# 09_-_USB.net
KiCad netlist of a schematic drawn in Altium Designer
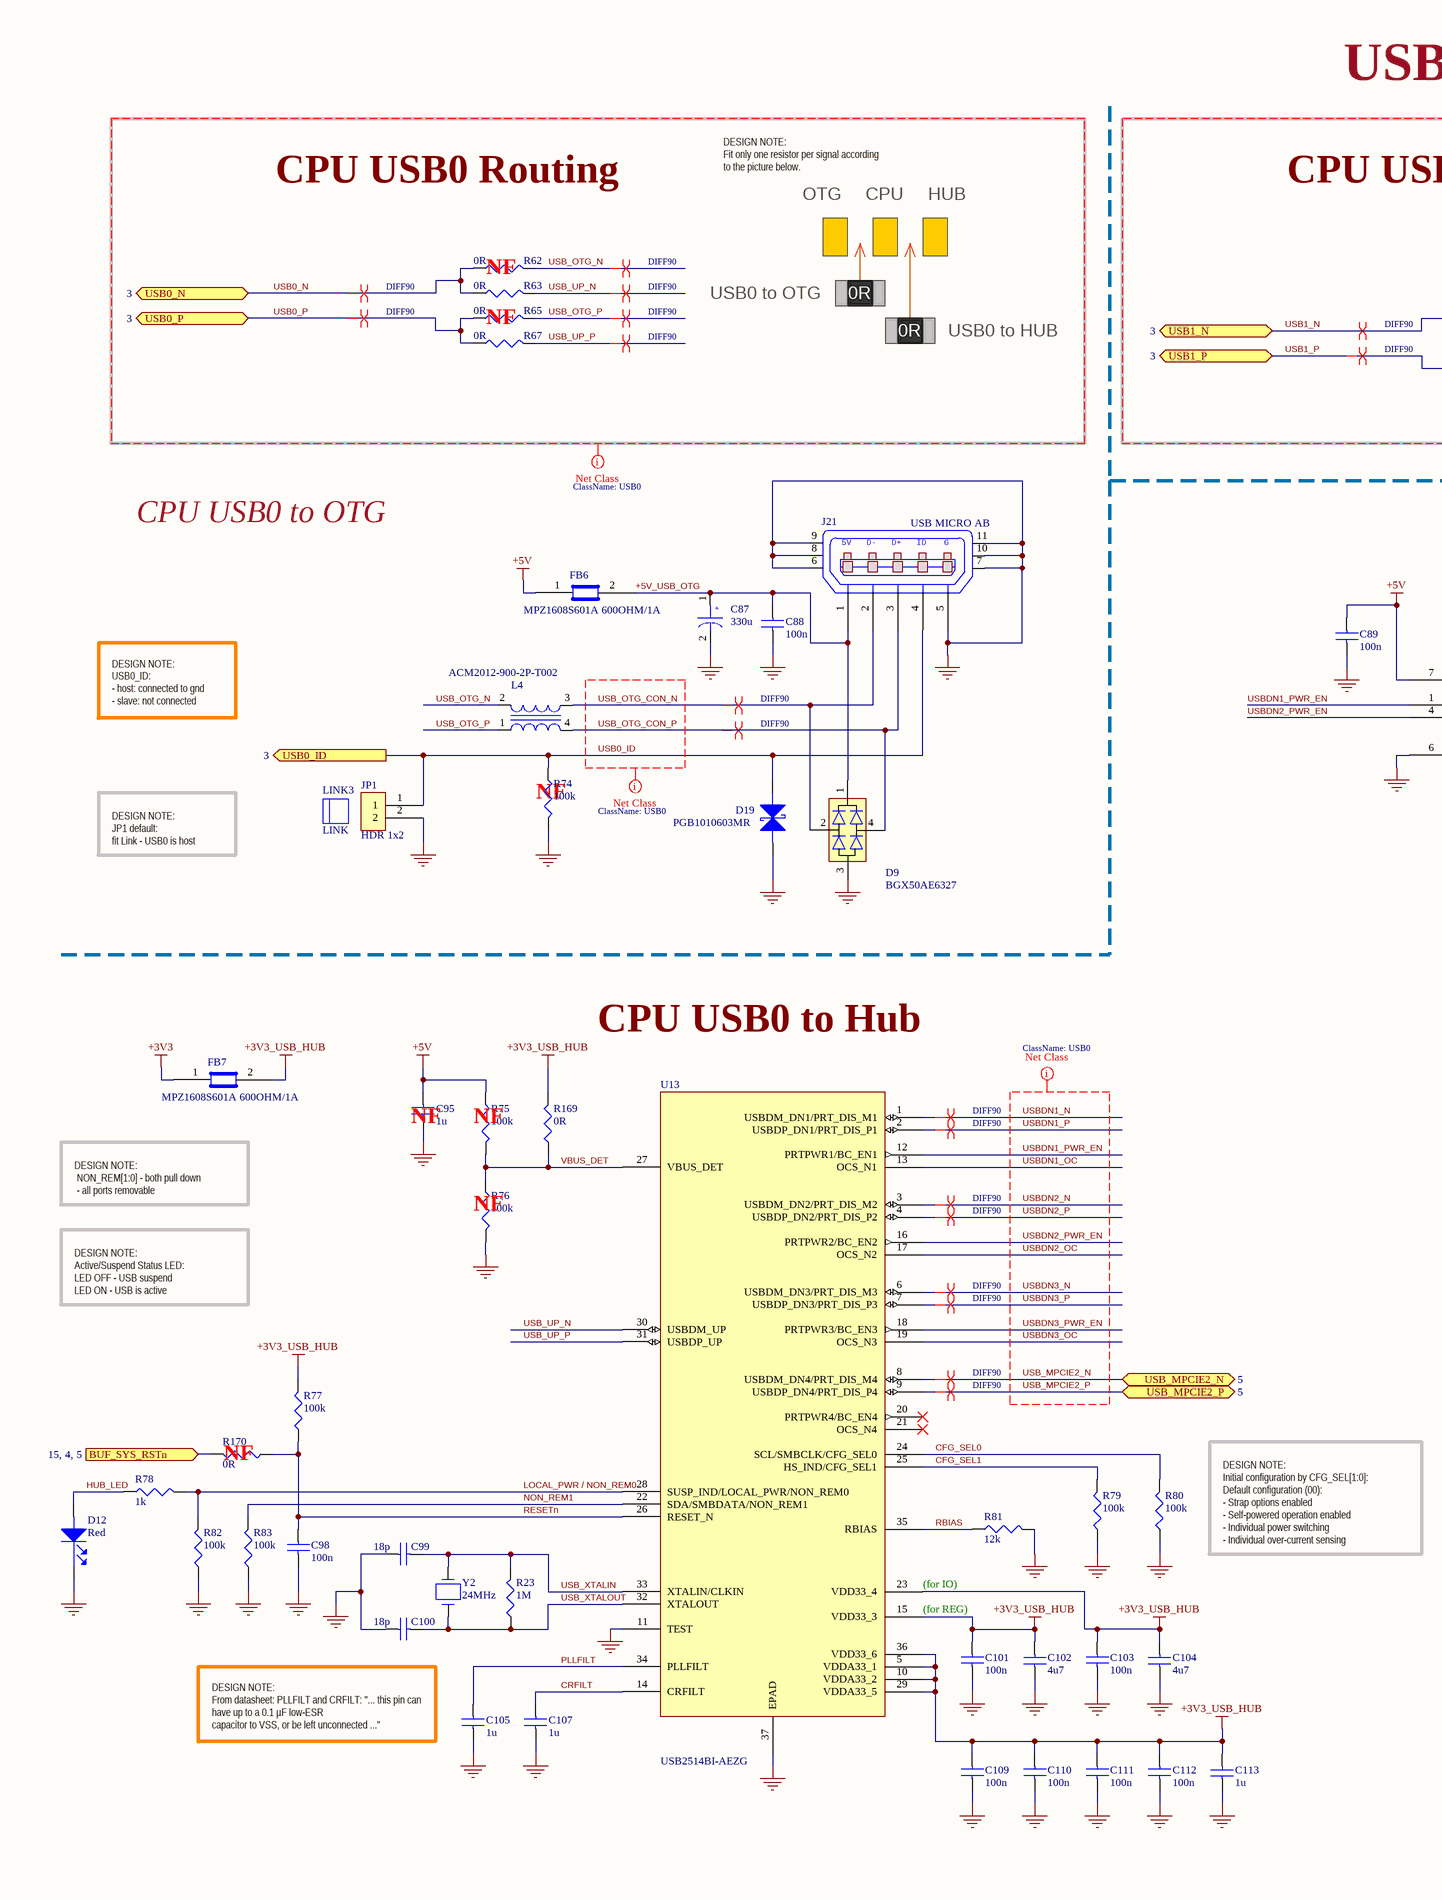
[diagram p0: [09] - USB.SchDoc, left]
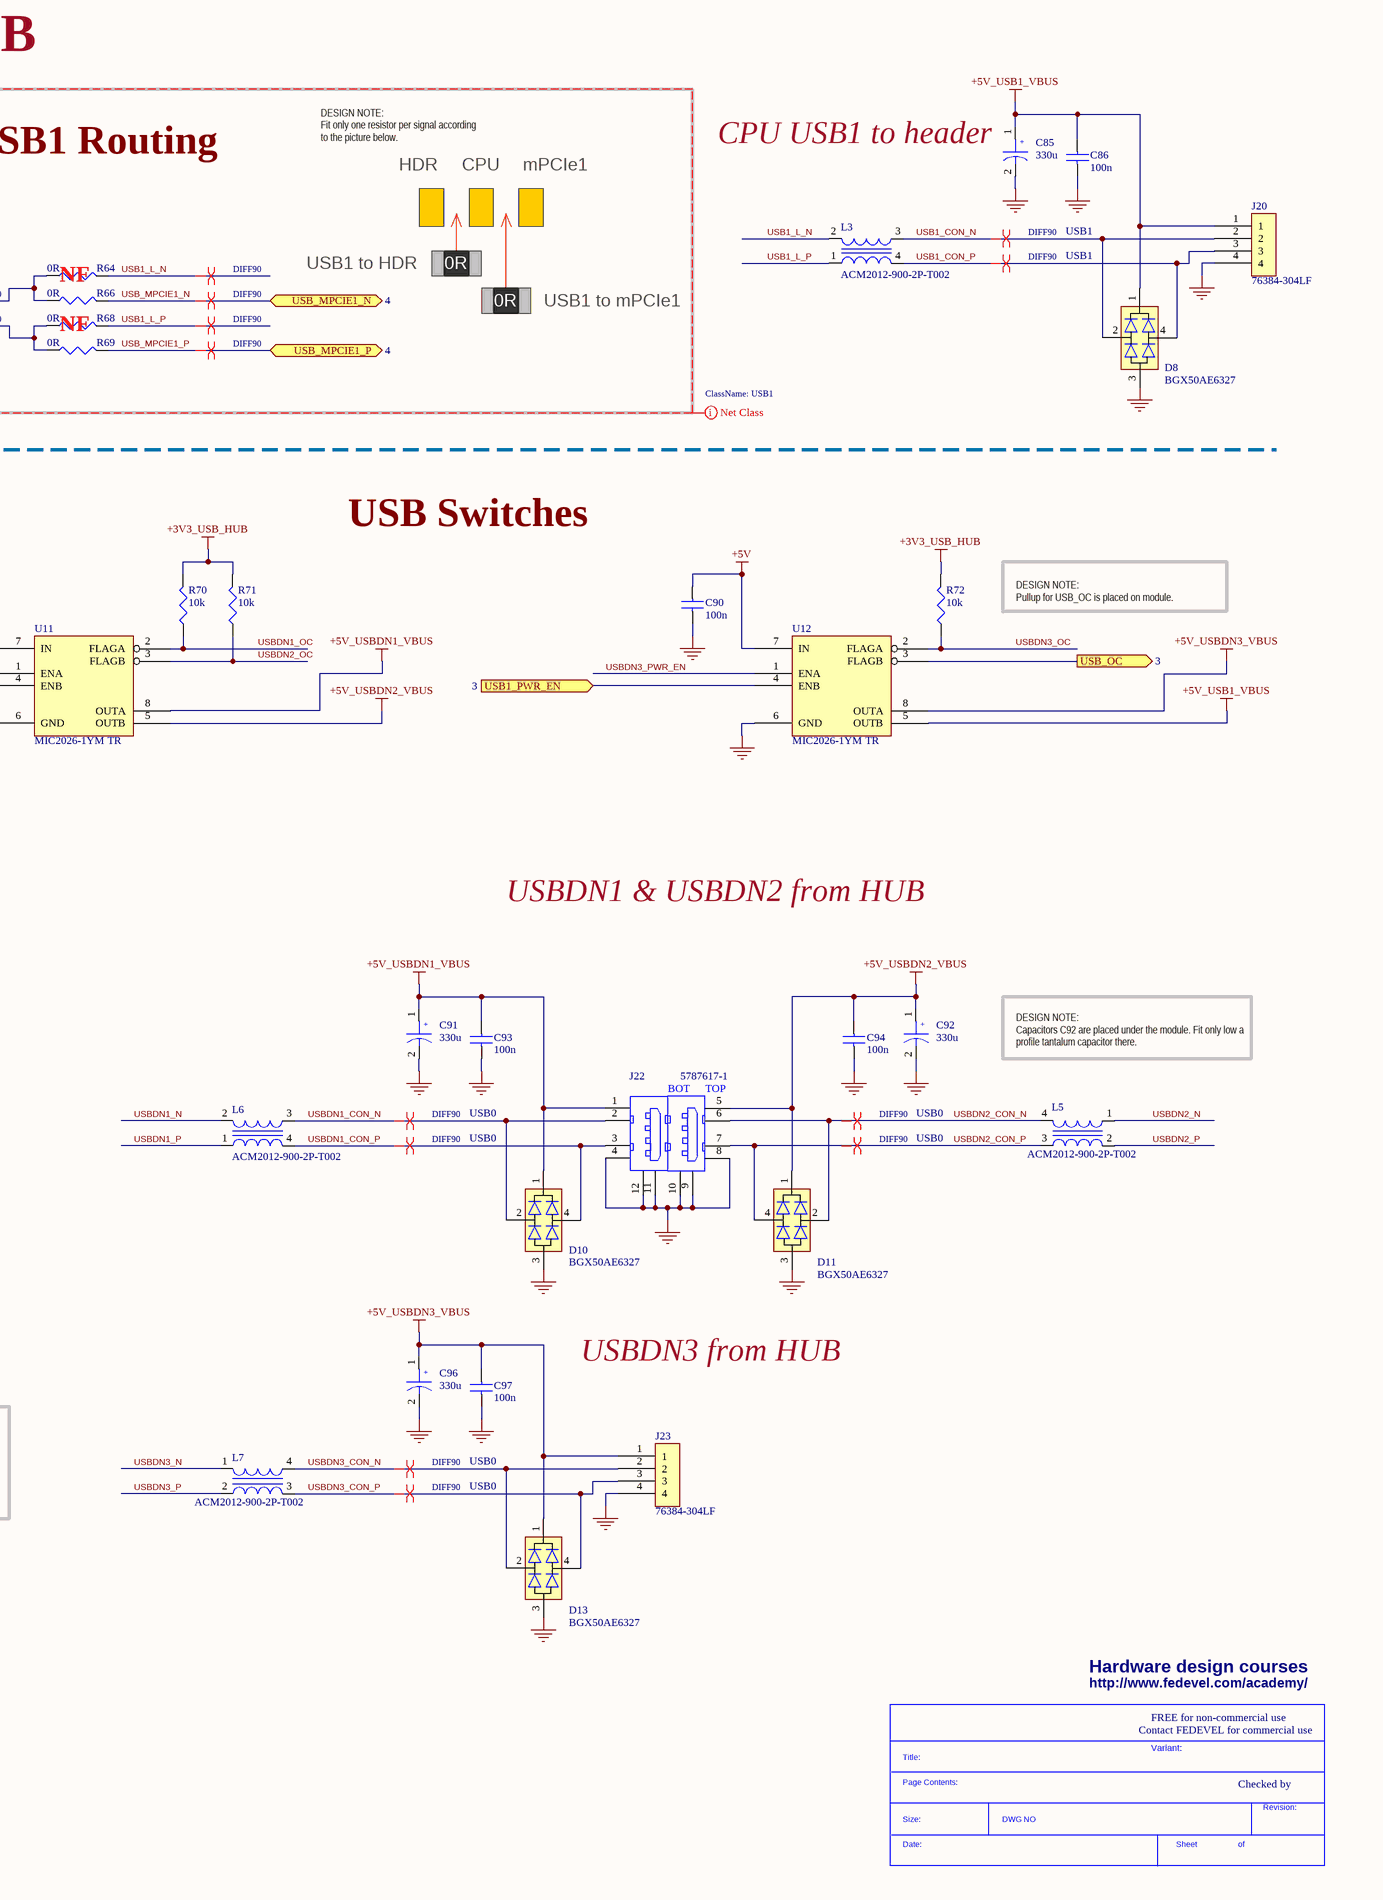
[diagram p1: [09] - USB.SchDoc, right]

(export (version "E")
  (design (tool "Eeschema 10.0.6"))
  (components
    (comp (ref "C85")
      (value "330u")
      (footprint "C2917")
      (description "CAP TANT 330UF 10V 10% 2917")
      (fields
        (field (name "MANUFACTURER") "Kemet")
        (field (name "MANUFACTURER PART NUMBER") "T495D337K010ATE150")
        (field (name ".CREATOR") "MM")
        (field (name ".CHECKED PCB") "MM")
        (field (name ".CHECKED SCH") "RF, used by MM")
      )
      (libsource (lib "Integrated_Library_RF_FEB_2012") (part "T495D337K010ATE150"))
    )
    (comp (ref "C86")
      (value "100n")
      (footprint "C0402")
      (description "CAP CER .10UF 50V X5R 10% 0402")
      (fields
        (field (name "MANUFACTURER") "TDK Corporation")
        (field (name "MANUFACTURER PART NUMBER") "C1005X5R1H104K")
      )
      (libsource (lib "Integrated_Library_RF_FEB_2012") (part "C1005X5R1H104K"))
    )
    (comp (ref "C87")
      (value "330u")
      (footprint "C2917")
      (description "CAP TANT 330UF 10V 10% 2917")
      (fields
        (field (name "MANUFACTURER") "Kemet")
        (field (name "MANUFACTURER PART NUMBER") "T495D337K010ATE150")
        (field (name ".CREATOR") "MM")
        (field (name ".CHECKED PCB") "MM")
        (field (name ".CHECKED SCH") "RF, used by MM")
      )
      (libsource (lib "Integrated_Library_RF_FEB_2012") (part "T495D337K010ATE150"))
    )
    (comp (ref "C88")
      (value "100n")
      (footprint "C0402")
      (description "CAP CER .10UF 50V X5R 10% 0402")
      (fields
        (field (name "MANUFACTURER") "TDK Corporation")
        (field (name "MANUFACTURER PART NUMBER") "C1005X5R1H104K")
      )
      (libsource (lib "Integrated_Library_RF_FEB_2012") (part "C1005X5R1H104K"))
    )
    (comp (ref "C89")
      (value "100n")
      (footprint "C0402")
      (description "CAP CER .10UF 50V X5R 10% 0402")
      (fields
        (field (name "MANUFACTURER") "TDK Corporation")
        (field (name "MANUFACTURER PART NUMBER") "C1005X5R1H104K")
      )
      (libsource (lib "Integrated_Library_RF_FEB_2012") (part "C1005X5R1H104K"))
    )
    (comp (ref "C90")
      (value "100n")
      (footprint "C0402")
      (description "CAP CER .10UF 50V X5R 10% 0402")
      (fields
        (field (name "MANUFACTURER") "TDK Corporation")
        (field (name "MANUFACTURER PART NUMBER") "C1005X5R1H104K")
      )
      (libsource (lib "Integrated_Library_RF_FEB_2012") (part "C1005X5R1H104K"))
    )
    (comp (ref "C91")
      (value "330u")
      (footprint "C2917")
      (description "CAP TANT 330UF 10V 10% 2917")
      (fields
        (field (name "MANUFACTURER") "Kemet")
        (field (name "MANUFACTURER PART NUMBER") "T495D337K010ATE150")
        (field (name ".CREATOR") "MM")
        (field (name ".CHECKED PCB") "MM")
        (field (name ".CHECKED SCH") "RF, used by MM")
      )
      (libsource (lib "Integrated_Library_RF_FEB_2012") (part "T495D337K010ATE150"))
    )
    (comp (ref "C92")
      (value "330u")
      (footprint "C2917")
      (description "CAP TANT 330UF 10V 10% 2917")
      (fields
        (field (name "MANUFACTURER") "Kemet")
        (field (name "MANUFACTURER PART NUMBER") "T495D337K010ATE150")
        (field (name ".CREATOR") "MM")
        (field (name ".CHECKED PCB") "MM")
        (field (name ".CHECKED SCH") "RF, used by MM")
      )
      (libsource (lib "Integrated_Library_RF_FEB_2012") (part "T495D337K010ATE150"))
    )
    (comp (ref "C93")
      (value "100n")
      (footprint "C0402")
      (description "CAP CER .10UF 50V X5R 10% 0402")
      (fields
        (field (name "MANUFACTURER") "TDK Corporation")
        (field (name "MANUFACTURER PART NUMBER") "C1005X5R1H104K")
      )
      (libsource (lib "Integrated_Library_RF_FEB_2012") (part "C1005X5R1H104K"))
    )
    (comp (ref "C94")
      (value "100n")
      (footprint "C0402")
      (description "CAP CER .10UF 50V X5R 10% 0402")
      (fields
        (field (name "MANUFACTURER") "TDK Corporation")
        (field (name "MANUFACTURER PART NUMBER") "C1005X5R1H104K")
      )
      (libsource (lib "Integrated_Library_RF_FEB_2012") (part "C1005X5R1H104K"))
    )
    (comp (ref "C95")
      (value "1u")
      (footprint "C0402")
      (description "CAP CER 1.0UF 16V X5R 0402")
      (fields
        (field (name "MANUFACTURER") "TDK Corporation")
        (field (name "MANUFACTURER PART NUMBER") "C1005X5R1C105K")
      )
      (libsource (lib "Integrated_Library_RF_FEB_2012") (part "C1005X5R1C105K"))
    )
    (comp (ref "C96")
      (value "330u")
      (footprint "C2917")
      (description "CAP TANT 330UF 10V 10% 2917")
      (fields
        (field (name "MANUFACTURER") "Kemet")
        (field (name "MANUFACTURER PART NUMBER") "T495D337K010ATE150")
        (field (name ".CREATOR") "MM")
        (field (name ".CHECKED PCB") "MM")
        (field (name ".CHECKED SCH") "RF, used by MM")
      )
      (libsource (lib "Integrated_Library_RF_FEB_2012") (part "T495D337K010ATE150"))
    )
    (comp (ref "C97")
      (value "100n")
      (footprint "C0402")
      (description "CAP CER .10UF 50V X5R 10% 0402")
      (fields
        (field (name "MANUFACTURER") "TDK Corporation")
        (field (name "MANUFACTURER PART NUMBER") "C1005X5R1H104K")
      )
      (libsource (lib "Integrated_Library_RF_FEB_2012") (part "C1005X5R1H104K"))
    )
    (comp (ref "C98")
      (value "100n")
      (footprint "C0402")
      (description "CAP CER .10UF 50V X5R 10% 0402")
      (fields
        (field (name "MANUFACTURER") "TDK Corporation")
        (field (name "MANUFACTURER PART NUMBER") "C1005X5R1H104K")
      )
      (libsource (lib "Integrated_Library_RF_FEB_2012") (part "C1005X5R1H104K"))
    )
    (comp (ref "C99")
      (value "18p")
      (footprint "C0402")
      (description "CAP CER 18PF 50V C0G 5% 0402")
      (fields
        (field (name "MANUFACTURER") "TDK Corporation")
        (field (name "MANUFACTURER PART NUMBER") "C1005C0G1H180J")
      )
      (libsource (lib "Integrated_Library_RF_FEB_2012") (part "C1005C0G1H180J"))
    )
    (comp (ref "C100")
      (value "18p")
      (footprint "C0402")
      (description "CAP CER 18PF 50V C0G 5% 0402")
      (fields
        (field (name "MANUFACTURER") "TDK Corporation")
        (field (name "MANUFACTURER PART NUMBER") "C1005C0G1H180J")
      )
      (libsource (lib "Integrated_Library_RF_FEB_2012") (part "C1005C0G1H180J"))
    )
    (comp (ref "C101")
      (value "100n")
      (footprint "C0402")
      (description "CAP CER .10UF 50V X5R 10% 0402")
      (fields
        (field (name "MANUFACTURER") "TDK Corporation")
        (field (name "MANUFACTURER PART NUMBER") "C1005X5R1H104K")
      )
      (libsource (lib "Integrated_Library_RF_FEB_2012") (part "C1005X5R1H104K"))
    )
    (comp (ref "C102")
      (value "4u7")
      (footprint "C0402")
      (description "CAP CER 4.7UF 10V 20% X5R 0402")
      (fields
        (field (name "MANUFACTURER") "TDK Corporation")
        (field (name "MANUFACTURER PART NUMBER") "C1005X5R1A475M")
        (field (name ".CHECKED PCB") "RF")
        (field (name ".CHECKED SCH") "RF")
      )
      (libsource (lib "Integrated_Library_RF_FEB_2012") (part "C1005X5R1A475M"))
    )
    (comp (ref "C103")
      (value "100n")
      (footprint "C0402")
      (description "CAP CER .10UF 50V X5R 10% 0402")
      (fields
        (field (name "MANUFACTURER") "TDK Corporation")
        (field (name "MANUFACTURER PART NUMBER") "C1005X5R1H104K")
      )
      (libsource (lib "Integrated_Library_RF_FEB_2012") (part "C1005X5R1H104K"))
    )
    (comp (ref "C104")
      (value "4u7")
      (footprint "C0402")
      (description "CAP CER 4.7UF 10V 20% X5R 0402")
      (fields
        (field (name "MANUFACTURER") "TDK Corporation")
        (field (name "MANUFACTURER PART NUMBER") "C1005X5R1A475M")
        (field (name ".CHECKED PCB") "RF")
        (field (name ".CHECKED SCH") "RF")
      )
      (libsource (lib "Integrated_Library_RF_FEB_2012") (part "C1005X5R1A475M"))
    )
    (comp (ref "C105")
      (value "1u")
      (footprint "C0402")
      (description "CAP CER 1.0UF 16V X5R 0402")
      (fields
        (field (name "MANUFACTURER") "TDK Corporation")
        (field (name "MANUFACTURER PART NUMBER") "C1005X5R1C105K")
      )
      (libsource (lib "Integrated_Library_RF_FEB_2012") (part "C1005X5R1C105K"))
    )
    (comp (ref "C107")
      (value "1u")
      (footprint "C0402")
      (description "CAP CER 1.0UF 16V X5R 0402")
      (fields
        (field (name "MANUFACTURER") "TDK Corporation")
        (field (name "MANUFACTURER PART NUMBER") "C1005X5R1C105K")
      )
      (libsource (lib "Integrated_Library_RF_FEB_2012") (part "C1005X5R1C105K"))
    )
    (comp (ref "C109")
      (value "100n")
      (footprint "C0402")
      (description "CAP CER .10UF 50V X5R 10% 0402")
      (fields
        (field (name "MANUFACTURER") "TDK Corporation")
        (field (name "MANUFACTURER PART NUMBER") "C1005X5R1H104K")
      )
      (libsource (lib "Integrated_Library_RF_FEB_2012") (part "C1005X5R1H104K"))
    )
    (comp (ref "C110")
      (value "100n")
      (footprint "C0402")
      (description "CAP CER .10UF 50V X5R 10% 0402")
      (fields
        (field (name "MANUFACTURER") "TDK Corporation")
        (field (name "MANUFACTURER PART NUMBER") "C1005X5R1H104K")
      )
      (libsource (lib "Integrated_Library_RF_FEB_2012") (part "C1005X5R1H104K"))
    )
    (comp (ref "C111")
      (value "100n")
      (footprint "C0402")
      (description "CAP CER .10UF 50V X5R 10% 0402")
      (fields
        (field (name "MANUFACTURER") "TDK Corporation")
        (field (name "MANUFACTURER PART NUMBER") "C1005X5R1H104K")
      )
      (libsource (lib "Integrated_Library_RF_FEB_2012") (part "C1005X5R1H104K"))
    )
    (comp (ref "C112")
      (value "100n")
      (footprint "C0402")
      (description "CAP CER .10UF 50V X5R 10% 0402")
      (fields
        (field (name "MANUFACTURER") "TDK Corporation")
        (field (name "MANUFACTURER PART NUMBER") "C1005X5R1H104K")
      )
      (libsource (lib "Integrated_Library_RF_FEB_2012") (part "C1005X5R1H104K"))
    )
    (comp (ref "C113")
      (value "1u")
      (footprint "C0402")
      (description "CAP CER 1.0UF 16V X5R 0402")
      (fields
        (field (name "MANUFACTURER") "TDK Corporation")
        (field (name "MANUFACTURER PART NUMBER") "C1005X5R1C105K")
      )
      (libsource (lib "Integrated_Library_RF_FEB_2012") (part "C1005X5R1C105K"))
    )
    (comp (ref "D8")
      (value "BGX50AE6327")
      (footprint "SOT143")
      (description "DIODE SWITCHING 50V SOT-143")
      (fields (field (name "MANUFACTURER") "Infineon Technologies"))
      (libsource (lib "Integrated_Library_RF_FEB_2012") (part "BGX50AE6327"))
    )
    (comp (ref "D9")
      (value "BGX50AE6327")
      (footprint "SOT143")
      (description "DIODE SWITCHING 50V SOT-143")
      (fields (field (name "MANUFACTURER") "Infineon Technologies"))
      (libsource (lib "Integrated_Library_RF_FEB_2012") (part "BGX50AE6327"))
    )
    (comp (ref "D10")
      (value "BGX50AE6327")
      (footprint "SOT143")
      (description "DIODE SWITCHING 50V SOT-143")
      (fields (field (name "MANUFACTURER") "Infineon Technologies"))
      (libsource (lib "Integrated_Library_RF_FEB_2012") (part "BGX50AE6327"))
    )
    (comp (ref "D11")
      (value "BGX50AE6327")
      (footprint "SOT143")
      (description "DIODE SWITCHING 50V SOT-143")
      (fields (field (name "MANUFACTURER") "Infineon Technologies"))
      (libsource (lib "") (part "BGX50AE6327_1"))
    )
    (comp (ref "D12")
      (value "Red")
      (footprint "LED_0603")
      (description "LED SMARTLED RED 630NM 0603 SMD")
      (fields
        (field (name "MANUFACTURER") "OSRAM Opto Semiconductors Inc")
        (field (name "MANUFACTURER PART NUMBER") "LS L29K-H1J2-1-Z")
        (field (name ".CHECKED PCB") "RF")
        (field (name ".CHECKED SCH") "RF")
      )
      (libsource (lib "Integrated_Library_RF_FEB_2012") (part "LS L29K-H1J2-1-Z"))
    )
    (comp (ref "D13")
      (value "BGX50AE6327")
      (footprint "SOT143")
      (description "DIODE SWITCHING 50V SOT-143")
      (fields (field (name "MANUFACTURER") "Infineon Technologies"))
      (libsource (lib "Integrated_Library_RF_FEB_2012") (part "BGX50AE6327"))
    )
    (comp (ref "D19")
      (value "PGB1010603MR")
      (footprint "C0603")
      (description "SUPPRESSOR ESD 24VDC 0603 SMD")
      (fields
        (field (name "MANUFACTURER") "Littelfuse Inc")
        (field (name ".CREATOR") "MM")
        (field (name ".CHECKED PCB") "MM")
        (field (name ".CHECKED SCH") "MM")
      )
      (libsource (lib "Integrated_Library_RF_FEB_2012") (part "PGB1010603MR"))
    )
    (comp (ref "FB6")
      (value "MPZ1608S601A 600OHM/1A")
      (footprint "C0603")
      (description "FERRITE CHIP BEAD 600 OHM SMD 1A")
      (fields
        (field (name "MANUFACTURER") "TDK Corporation")
        (field (name "MANUFACTURER PART NUMBER") "MPZ1608S601A")
        (field (name ".CHECKED PCB") "RF")
        (field (name ".CHECKED SCH") "RF")
      )
      (libsource (lib "Integrated_Library_RF_FEB_2012") (part "MPZ1608S601A"))
    )
    (comp (ref "FB7")
      (value "MPZ1608S601A 600OHM/1A")
      (footprint "C0603")
      (description "FERRITE CHIP BEAD 600 OHM SMD 1A")
      (fields
        (field (name "MANUFACTURER") "TDK Corporation")
        (field (name "MANUFACTURER PART NUMBER") "MPZ1608S601A")
        (field (name ".CHECKED PCB") "RF")
        (field (name ".CHECKED SCH") "RF")
      )
      (libsource (lib "Integrated_Library_RF_FEB_2012") (part "MPZ1608S601A"))
    )
    (comp (ref "J20")
      (value "76384-304LF")
      (footprint "HDR_1x4_2.54MM_SHDR")
      (description "CONN HEADER 4POS .100\" STR GOLD")
      (fields
        (field (name "MANUFACTURER") "FCI")
        (field (name ".CHECKED PCB") "RF")
        (field (name ".CHECKED SCH") "RF")
      )
      (libsource (lib "Integrated_Library_RF_FEB_2012") (part "76384-304LF"))
    )
    (comp (ref "J21")
      (value "USB MICRO AB")
      (footprint "USB_Micro_AB")
      (description "CONN RCPT MICRO USB AB R/A SMD")
      (fields
        (field (name "MANUFACTURER") "Molex Inc")
        (field (name "MANUFACTURER PART NUMBER") "0475890001")
        (field (name ".CREATOR") "MM")
        (field (name ".CHECKED PCB") "MM")
        (field (name ".CHECKED SCH") "MM")
      )
      (libsource (lib "Integrated_Library_RF_FEB_2012") (part "0475890001"))
    )
    (comp (ref "J22")
      (value "5787617-1")
      (footprint "USB-2A")
      (description "CONN RCPT R/A 4OVER4POS GOLD PCB")
      (fields (field (name "MANUFACTURER") "TE Connectivity"))
      (libsource (lib "Integrated_Library_RF_FEB_2012") (part "5787617-1"))
    )
    (comp (ref "J23")
      (value "76384-304LF")
      (footprint "HDR_1x4_2.54MM_SHDR")
      (description "CONN HEADER 4POS .100\" STR GOLD")
      (fields
        (field (name "MANUFACTURER") "FCI")
        (field (name ".CHECKED PCB") "RF")
        (field (name ".CHECKED SCH") "RF")
      )
      (libsource (lib "Integrated_Library_RF_FEB_2012") (part "76384-304LF"))
    )
    (comp (ref "JP1")
      (value "HDR 1x2")
      (footprint "HDR_1x2_2.54MM")
      (description "BERGSTIK II .100\" SR STRAIGHT")
      (fields
        (field (name "MANUFACTURER") "FCI")
        (field (name "MANUFACTURER PART NUMBER") "68001-202HLF")
        (field (name ".CHECKED PCB") "RF")
        (field (name ".CHECKED SCH") "RF")
      )
      (libsource (lib "Integrated_Library_RF_FEB_2012") (part "68001-202HLF"))
    )
    (comp (ref "L3")
      (value "ACM2012-900-2P-T002")
      (footprint "ACM2012")
      (description "CHOKE COMM MODE 90 OHM .4A SMD")
      (fields
        (field (name "MANUFACTURER") "TDK Corporation")
        (field (name "TOLERANCE") "±1%")
        (field (name ".CHECKED PCB") "RF")
        (field (name ".CHECKED SCH") "RF")
      )
      (libsource (lib "Integrated_Library_RF_FEB_2012") (part "ACM2012-900-2P-T002"))
    )
    (comp (ref "L4")
      (value "ACM2012-900-2P-T002")
      (footprint "ACM2012")
      (description "CHOKE COMM MODE 90 OHM .4A SMD")
      (fields
        (field (name "MANUFACTURER") "TDK Corporation")
        (field (name "TOLERANCE") "±1%")
        (field (name ".CHECKED PCB") "RF")
        (field (name ".CHECKED SCH") "RF")
      )
      (libsource (lib "Integrated_Library_RF_FEB_2012") (part "ACM2012-900-2P-T002"))
    )
    (comp (ref "L5")
      (value "ACM2012-900-2P-T002")
      (footprint "ACM2012")
      (description "CHOKE COMM MODE 90 OHM .4A SMD")
      (fields
        (field (name "MANUFACTURER") "TDK Corporation")
        (field (name "TOLERANCE") "±1%")
        (field (name ".CHECKED PCB") "RF")
        (field (name ".CHECKED SCH") "RF")
      )
      (libsource (lib "Integrated_Library_RF_FEB_2012") (part "ACM2012-900-2P-T002"))
    )
    (comp (ref "L6")
      (value "ACM2012-900-2P-T002")
      (footprint "ACM2012")
      (description "CHOKE COMM MODE 90 OHM .4A SMD")
      (fields
        (field (name "MANUFACTURER") "TDK Corporation")
        (field (name "TOLERANCE") "±1%")
        (field (name ".CHECKED PCB") "RF")
        (field (name ".CHECKED SCH") "RF")
      )
      (libsource (lib "Integrated_Library_RF_FEB_2012") (part "ACM2012-900-2P-T002"))
    )
    (comp (ref "L7")
      (value "ACM2012-900-2P-T002")
      (footprint "ACM2012")
      (description "CHOKE COMM MODE 90 OHM .4A SMD")
      (fields
        (field (name "MANUFACTURER") "TDK Corporation")
        (field (name "TOLERANCE") "±1%")
        (field (name ".CHECKED PCB") "RF")
        (field (name ".CHECKED SCH") "RF")
      )
      (libsource (lib "") (part "ACM2012-900-2P-T002_1"))
    )
    (comp (ref "LINK3")
      (value "LINK")
      (description "CONN JUMPER SHORTING .100\" GOLD")
      (fields
        (field (name "MANUFACTURER") "Sullins Connector Solutions")
        (field (name "MANUFACTURER PART NUMBER") "QPC02SXGN-RC")
        (field (name ".CHECKED SCH") "RF")
      )
      (libsource (lib "Integrated_Library_RF_FEB_2012") (part "QPC02SXGN-RC"))
    )
    (comp (ref "R23")
      (value "1M")
      (footprint "R0402")
      (description "RES 1.00M OHM 1/16W 1% 0402 SMD")
      (fields
        (field (name "MANUFACTURER") "Yageo")
        (field (name "MANUFACTURER PART NUMBER") "RC0402FR-071ML")
        (field (name ".CHECKED PCB") "RF")
        (field (name ".CHECKED SCH") "RF")
      )
      (libsource (lib "Integrated_Library_RF_FEB_2012") (part "RC0402FR-071ML"))
    )
    (comp (ref "R62")
      (value "0R")
      (footprint "R0402")
      (description "RES 0.0 OHM 1/16W 0402 SMD")
      (fields
        (field (name "MANUFACTURER") "Yageo")
        (field (name "MANUFACTURER PART NUMBER") "RC0402JR-070RL")
      )
      (libsource (lib "Integrated_Library_RF_FEB_2012") (part "RC0402JR-070RL"))
    )
    (comp (ref "R63")
      (value "0R")
      (footprint "R0402")
      (description "RES 0.0 OHM 1/16W 0402 SMD")
      (fields
        (field (name "MANUFACTURER") "Yageo")
        (field (name "MANUFACTURER PART NUMBER") "RC0402JR-070RL")
      )
      (libsource (lib "Integrated_Library_RF_FEB_2012") (part "RC0402JR-070RL"))
    )
    (comp (ref "R64")
      (value "0R")
      (footprint "R0402")
      (description "RES 0.0 OHM 1/16W 0402 SMD")
      (fields
        (field (name "MANUFACTURER") "Yageo")
        (field (name "MANUFACTURER PART NUMBER") "RC0402JR-070RL")
      )
      (libsource (lib "Integrated_Library_RF_FEB_2012") (part "RC0402JR-070RL"))
    )
    (comp (ref "R65")
      (value "0R")
      (footprint "R0402")
      (description "RES 0.0 OHM 1/16W 0402 SMD")
      (fields
        (field (name "MANUFACTURER") "Yageo")
        (field (name "MANUFACTURER PART NUMBER") "RC0402JR-070RL")
      )
      (libsource (lib "Integrated_Library_RF_FEB_2012") (part "RC0402JR-070RL"))
    )
    (comp (ref "R66")
      (value "0R")
      (footprint "R0402")
      (description "RES 0.0 OHM 1/16W 0402 SMD")
      (fields
        (field (name "MANUFACTURER") "Yageo")
        (field (name "MANUFACTURER PART NUMBER") "RC0402JR-070RL")
      )
      (libsource (lib "Integrated_Library_RF_FEB_2012") (part "RC0402JR-070RL"))
    )
    (comp (ref "R67")
      (value "0R")
      (footprint "R0402")
      (description "RES 0.0 OHM 1/16W 0402 SMD")
      (fields
        (field (name "MANUFACTURER") "Yageo")
        (field (name "MANUFACTURER PART NUMBER") "RC0402JR-070RL")
      )
      (libsource (lib "Integrated_Library_RF_FEB_2012") (part "RC0402JR-070RL"))
    )
    (comp (ref "R68")
      (value "0R")
      (footprint "R0402")
      (description "RES 0.0 OHM 1/16W 0402 SMD")
      (fields
        (field (name "MANUFACTURER") "Yageo")
        (field (name "MANUFACTURER PART NUMBER") "RC0402JR-070RL")
      )
      (libsource (lib "Integrated_Library_RF_FEB_2012") (part "RC0402JR-070RL"))
    )
    (comp (ref "R69")
      (value "0R")
      (footprint "R0402")
      (description "RES 0.0 OHM 1/16W 0402 SMD")
      (fields
        (field (name "MANUFACTURER") "Yageo")
        (field (name "MANUFACTURER PART NUMBER") "RC0402JR-070RL")
      )
      (libsource (lib "Integrated_Library_RF_FEB_2012") (part "RC0402JR-070RL"))
    )
    (comp (ref "R70")
      (value "10k")
      (footprint "R0402")
      (description "RES 10.0K OHM 1/16W 1% 0402 SMD")
      (fields
        (field (name "MANUFACTURER") "Yageo")
        (field (name "MANUFACTURER PART NUMBER") "RC0402FR-0710KL")
      )
      (libsource (lib "Integrated_Library_RF_FEB_2012") (part "RC0402FR-0710KL"))
    )
    (comp (ref "R71")
      (value "10k")
      (footprint "R0402")
      (description "RES 10.0K OHM 1/16W 1% 0402 SMD")
      (fields
        (field (name "MANUFACTURER") "Yageo")
        (field (name "MANUFACTURER PART NUMBER") "RC0402FR-0710KL")
      )
      (libsource (lib "Integrated_Library_RF_FEB_2012") (part "RC0402FR-0710KL"))
    )
    (comp (ref "R72")
      (value "10k")
      (footprint "R0402")
      (description "RES 10.0K OHM 1/16W 1% 0402 SMD")
      (fields
        (field (name "MANUFACTURER") "Yageo")
        (field (name "MANUFACTURER PART NUMBER") "RC0402FR-0710KL")
      )
      (libsource (lib "Integrated_Library_RF_FEB_2012") (part "RC0402FR-0710KL"))
    )
    (comp (ref "R74")
      (value "100k")
      (footprint "R0402")
      (description "RES 100K OHM 1/16W 1% 0402 SMD")
      (fields
        (field (name "MANUFACTURER") "Stackpole Electronics Inc")
        (field (name "MANUFACTURER PART NUMBER") "RMCF0402FT100K")
      )
      (libsource (lib "Integrated_Library_RF_FEB_2012") (part "RMCF0402FT100K"))
    )
    (comp (ref "R75")
      (value "100k")
      (footprint "R0402")
      (description "RES 100K OHM 1/16W 1% 0402 SMD")
      (fields
        (field (name "MANUFACTURER") "Stackpole Electronics Inc")
        (field (name "MANUFACTURER PART NUMBER") "RMCF0402FT100K")
      )
      (libsource (lib "Integrated_Library_RF_FEB_2012") (part "RMCF0402FT100K"))
    )
    (comp (ref "R76")
      (value "100k")
      (footprint "R0402")
      (description "RES 100K OHM 1/16W 1% 0402 SMD")
      (fields
        (field (name "MANUFACTURER") "Stackpole Electronics Inc")
        (field (name "MANUFACTURER PART NUMBER") "RMCF0402FT100K")
      )
      (libsource (lib "Integrated_Library_RF_FEB_2012") (part "RMCF0402FT100K"))
    )
    (comp (ref "R77")
      (value "100k")
      (footprint "R0402")
      (description "RES 100K OHM 1/16W 1% 0402 SMD")
      (fields
        (field (name "MANUFACTURER") "Stackpole Electronics Inc")
        (field (name "MANUFACTURER PART NUMBER") "RMCF0402FT100K")
      )
      (libsource (lib "Integrated_Library_RF_FEB_2012") (part "RMCF0402FT100K"))
    )
    (comp (ref "R78")
      (value "1k")
      (footprint "R0402")
      (description "RES 1.00K OHM 1/16W 1% 0402 SMD")
      (fields
        (field (name "MANUFACTURER") "Yageo")
        (field (name "MANUFACTURER PART NUMBER") "RC0402FR-071KL")
      )
      (libsource (lib "Integrated_Library_RF_FEB_2012") (part "RC0402FR-071KL"))
    )
    (comp (ref "R79")
      (value "100k")
      (footprint "R0402")
      (description "RES 100K OHM 1/16W 1% 0402 SMD")
      (fields
        (field (name "MANUFACTURER") "Stackpole Electronics Inc")
        (field (name "MANUFACTURER PART NUMBER") "RMCF0402FT100K")
      )
      (libsource (lib "Integrated_Library_RF_FEB_2012") (part "RMCF0402FT100K"))
    )
    (comp (ref "R80")
      (value "100k")
      (footprint "R0402")
      (description "RES 100K OHM 1/16W 1% 0402 SMD")
      (fields
        (field (name "MANUFACTURER") "Stackpole Electronics Inc")
        (field (name "MANUFACTURER PART NUMBER") "RMCF0402FT100K")
      )
      (libsource (lib "Integrated_Library_RF_FEB_2012") (part "RMCF0402FT100K"))
    )
    (comp (ref "R81")
      (value "12k")
      (footprint "R0402")
      (description "RES 12.0K OHM 1/16W 1% 0402 SMD")
      (fields
        (field (name "MANUFACTURER") "Yageo")
        (field (name "MANUFACTURER PART NUMBER") "RC0402FR-0712KL")
      )
      (libsource (lib "Integrated_Library_RF_FEB_2012") (part "RC0402FR-0712KL"))
    )
    (comp (ref "R82")
      (value "100k")
      (footprint "R0402")
      (description "RES 100K OHM 1/16W 1% 0402 SMD")
      (fields
        (field (name "MANUFACTURER") "Stackpole Electronics Inc")
        (field (name "MANUFACTURER PART NUMBER") "RMCF0402FT100K")
      )
      (libsource (lib "Integrated_Library_RF_FEB_2012") (part "RMCF0402FT100K"))
    )
    (comp (ref "R83")
      (value "100k")
      (footprint "R0402")
      (description "RES 100K OHM 1/16W 1% 0402 SMD")
      (fields
        (field (name "MANUFACTURER") "Stackpole Electronics Inc")
        (field (name "MANUFACTURER PART NUMBER") "RMCF0402FT100K")
      )
      (libsource (lib "Integrated_Library_RF_FEB_2012") (part "RMCF0402FT100K"))
    )
    (comp (ref "R169")
      (value "0R")
      (footprint "R0402")
      (description "RES 0.0 OHM 1/16W 0402 SMD")
      (fields
        (field (name "MANUFACTURER") "Yageo")
        (field (name "MANUFACTURER PART NUMBER") "RC0402JR-070RL")
      )
      (libsource (lib "Integrated_Library_RF_FEB_2012") (part "RC0402JR-070RL"))
    )
    (comp (ref "R170")
      (value "0R")
      (footprint "R0402")
      (description "RES 0.0 OHM 1/16W 0402 SMD")
      (fields
        (field (name "MANUFACTURER") "Yageo")
        (field (name "MANUFACTURER PART NUMBER") "RC0402JR-070RL")
      )
      (libsource (lib "Integrated_Library_RF_FEB_2012") (part "RC0402JR-070RL"))
    )
    (comp (ref "U11")
      (value "MIC2026-1YM TR")
      (footprint "8_SOIC_3.9MM")
      (description "IC SW DISTRIBUTION 2CHAN 8SOIC")
      (fields (field (name "MANUFACTURER") "Micrel Inc"))
      (libsource (lib "Integrated_Library_RF_FEB_2012") (part "MIC2026-1YM TR"))
    )
    (comp (ref "U12")
      (value "MIC2026-1YM TR")
      (footprint "8_SOIC_3.9MM")
      (description "IC SW DISTRIBUTION 2CHAN 8SOIC")
      (fields (field (name "MANUFACTURER") "Micrel Inc"))
      (libsource (lib "Integrated_Library_RF_FEB_2012") (part "MIC2026-1YM TR"))
    )
    (comp (ref "U13")
      (value "USB2514BI-AEZG")
      (footprint "QFN36_6mmx6mm")
      (description "USB HUB CONT IND TEMP 36QFNE3")
      (fields
        (field (name "MANUFACTURER") "Microchip Technology")
        (field (name ".CREATOR") "MM")
        (field (name ".CHECKED PCB") "MM")
        (field (name ".CHECKED SCH") "MM")
      )
      (libsource (lib "Integrated_Library_RF_FEB_2012") (part "USB2514BI-AEZG"))
    )
    (comp (ref "Y2")
      (value "24MHz")
      (footprint "ABM7_v1_1")
      (description "CRYSTAL 24.0000MHZ 18PF SMD")
      (fields
        (field (name "MANUFACTURER") "Abracon Corporation")
        (field (name "MANUFACTURER PART NUMBER") "ABM7-24.000MHZ-D-2-Y-T")
        (field (name ".CREATOR") "MM")
        (field (name ".CHECKED PCB") "RF, used by MM")
        (field (name ".CHECKED SCH") "MM, checked by RF")
      )
      (libsource (lib "Integrated_Library_RF_FEB_2012") (part "ABM7-24.000MHZ-D-2-Y-T"))
    )
  )
  (nets
    (net (code "1") (name "+3V3") (class "Default")
      (node (ref "FB7") (pin "1") (pinfunction "1_1") (pintype "passive"))
    )
    (net (code "2") (name "+3V3_USB_HUB") (class "Default")
      (node (ref "C101") (pin "1") (pinfunction "1_1") (pintype "passive"))
      (node (ref "C102") (pin "2") (pinfunction "2_2") (pintype "passive"))
      (node (ref "C103") (pin "1") (pinfunction "1_1") (pintype "passive"))
      (node (ref "C104") (pin "2") (pinfunction "2_2") (pintype "passive"))
      (node (ref "C109") (pin "1") (pinfunction "1_1") (pintype "passive"))
      (node (ref "C110") (pin "1") (pinfunction "1_1") (pintype "passive"))
      (node (ref "C111") (pin "1") (pinfunction "1_1") (pintype "passive"))
      (node (ref "C112") (pin "1") (pinfunction "1_1") (pintype "passive"))
      (node (ref "C113") (pin "2") (pinfunction "2_2") (pintype "passive"))
      (node (ref "FB7") (pin "2") (pinfunction "2_2") (pintype "passive"))
      (node (ref "R169") (pin "2") (pinfunction "2_2") (pintype "passive"))
      (node (ref "R70") (pin "2") (pinfunction "2_2") (pintype "passive"))
      (node (ref "R71") (pin "2") (pinfunction "2_2") (pintype "passive"))
      (node (ref "R72") (pin "2") (pinfunction "2_2") (pintype "passive"))
      (node (ref "R77") (pin "2") (pinfunction "2_2") (pintype "passive"))
      (node (ref "U13") (pin "10") (pinfunction "VDDA33_2_10") (pintype "passive"))
      (node (ref "U13") (pin "15") (pinfunction "VDD33_3_15") (pintype "passive"))
      (node (ref "U13") (pin "23") (pinfunction "VDD33_4_23") (pintype "passive"))
      (node (ref "U13") (pin "29") (pinfunction "VDDA33_5_29") (pintype "passive"))
      (node (ref "U13") (pin "36") (pinfunction "VDD33_6_36") (pintype "passive"))
      (node (ref "U13") (pin "5") (pinfunction "VDDA33_1_5") (pintype "passive"))
    )
    (net (code "3") (name "+5V") (class "Default")
      (node (ref "C89") (pin "1") (pinfunction "1_1") (pintype "passive"))
      (node (ref "C90") (pin "1") (pinfunction "1_1") (pintype "passive"))
      (node (ref "C95") (pin "1") (pinfunction "1_1") (pintype "passive"))
      (node (ref "FB6") (pin "1") (pinfunction "1_1") (pintype "passive"))
      (node (ref "R75") (pin "1") (pinfunction "1_1") (pintype "passive"))
      (node (ref "U11") (pin "7") (pinfunction "IN_7") (pintype "power_in"))
      (node (ref "U12") (pin "7") (pinfunction "IN_7") (pintype "power_in"))
    )
    (net (code "4") (name "+5V_USB1_VBUS") (class "Default")
      (node (ref "C85") (pin "1") (pinfunction "1_1") (pintype "passive"))
      (node (ref "C86") (pin "1") (pinfunction "1_1") (pintype "passive"))
      (node (ref "D8") (pin "1") (pinfunction "1_1") (pintype "passive"))
      (node (ref "J20") (pin "1") (pinfunction "1_1") (pintype "passive"))
      (node (ref "U12") (pin "5") (pinfunction "OUTB_5") (pintype "passive"))
    )
    (net (code "5") (name "+5V_USBDN1_VBUS") (class "Default")
      (node (ref "C91") (pin "1") (pinfunction "1_1") (pintype "passive"))
      (node (ref "C93") (pin "1") (pinfunction "1_1") (pintype "passive"))
      (node (ref "D10") (pin "1") (pinfunction "1_1") (pintype "passive"))
      (node (ref "J22") (pin "1") (pinfunction "VBUS_1") (pintype "passive"))
      (node (ref "U11") (pin "8") (pinfunction "OUTA_8") (pintype "passive"))
    )
    (net (code "6") (name "+5V_USBDN2_VBUS") (class "Default")
      (node (ref "C92") (pin "1") (pinfunction "1_1") (pintype "passive"))
      (node (ref "C94") (pin "1") (pinfunction "1_1") (pintype "passive"))
      (node (ref "D11") (pin "1") (pinfunction "1_1") (pintype "passive"))
      (node (ref "J22") (pin "5") (pinfunction "VBUS2_5") (pintype "passive"))
      (node (ref "U11") (pin "5") (pinfunction "OUTB_5") (pintype "passive"))
    )
    (net (code "7") (name "+5V_USBDN3_VBUS") (class "Default")
      (node (ref "C96") (pin "1") (pinfunction "1_1") (pintype "passive"))
      (node (ref "C97") (pin "1") (pinfunction "1_1") (pintype "passive"))
      (node (ref "D13") (pin "1") (pinfunction "1_1") (pintype "passive"))
      (node (ref "J23") (pin "1") (pinfunction "1_1") (pintype "passive"))
      (node (ref "U12") (pin "8") (pinfunction "OUTA_8") (pintype "passive"))
    )
    (net (code "8") (name "/+5V_USB_OTG") (class "Default")
      (node (ref "C87") (pin "1") (pinfunction "1_1") (pintype "passive"))
      (node (ref "C88") (pin "1") (pinfunction "1_1") (pintype "passive"))
      (node (ref "D9") (pin "1") (pinfunction "1_1") (pintype "passive"))
      (node (ref "FB6") (pin "2") (pinfunction "2_2") (pintype "passive"))
      (node (ref "J21") (pin "1") (pinfunction "P1_1") (pintype "passive"))
    )
    (net (code "9") (name "/BUF_SYS_RSTn") (class "Default")
      (node (ref "R170") (pin "2") (pinfunction "2_2") (pintype "passive"))
    )
    (net (code "10") (name "/CFG_SEL0") (class "Default")
      (node (ref "R80") (pin "2") (pinfunction "2_2") (pintype "passive"))
      (node (ref "U13") (pin "24") (pinfunction "SCL/SMBCLK/CFG_SEL0_24") (pintype "passive"))
    )
    (net (code "11") (name "/CFG_SEL1") (class "Default")
      (node (ref "R79") (pin "2") (pinfunction "2_2") (pintype "passive"))
      (node (ref "U13") (pin "25") (pinfunction "HS_IND/CFG_SEL1_25") (pintype "passive"))
    )
    (net (code "12") (name "/CRFILT") (class "Default")
      (node (ref "C107") (pin "1") (pinfunction "1_1") (pintype "passive"))
      (node (ref "U13") (pin "14") (pinfunction "CRFILT_14") (pintype "passive"))
    )
    (net (code "13") (name "/HUB_LED") (class "Default")
      (node (ref "D12") (pin "2") (pinfunction "ANODE_2") (pintype "passive"))
      (node (ref "R78") (pin "1") (pinfunction "1_1") (pintype "passive"))
    )
    (net (code "14") (name "/LOCAL_PWR {slash} NON_REM0") (class "Default")
      (node (ref "R78") (pin "2") (pinfunction "2_2") (pintype "passive"))
      (node (ref "R82") (pin "2") (pinfunction "2_2") (pintype "passive"))
      (node (ref "U13") (pin "28") (pinfunction "SUSP_IND/LOCAL_PWR/NON_REM0_28") (pintype "passive"))
    )
    (net (code "15") (name "/NON_REM1") (class "Default")
      (node (ref "R83") (pin "2") (pinfunction "2_2") (pintype "passive"))
      (node (ref "U13") (pin "22") (pinfunction "SDA/SMBDATA/NON_REM1_22") (pintype "passive"))
    )
    (net (code "16") (name "/PLLFILT") (class "Default")
      (node (ref "C105") (pin "1") (pinfunction "1_1") (pintype "passive"))
      (node (ref "U13") (pin "34") (pinfunction "PLLFILT_34") (pintype "passive"))
    )
    (net (code "17") (name "/RBIAS") (class "Default")
      (node (ref "R81") (pin "1") (pinfunction "1_1") (pintype "passive"))
      (node (ref "U13") (pin "35") (pinfunction "RBIAS_35") (pintype "passive"))
    )
    (net (code "18") (name "/RESETn") (class "Default")
      (node (ref "C98") (pin "1") (pinfunction "1_1") (pintype "passive"))
      (node (ref "R170") (pin "1") (pinfunction "1_1") (pintype "passive"))
      (node (ref "R77") (pin "1") (pinfunction "1_1") (pintype "passive"))
      (node (ref "U13") (pin "26") (pinfunction "RESET_N_26") (pintype "passive"))
    )
    (net (code "19") (name "/USB0_ID") (class "Default")
      (node (ref "D19") (pin "1") (pinfunction "1_1") (pintype "passive"))
      (node (ref "J21") (pin "4") (pinfunction "P4_4") (pintype "passive"))
      (node (ref "JP1") (pin "1") (pinfunction "1_1") (pintype "passive"))
      (node (ref "R74") (pin "1") (pinfunction "1_1") (pintype "passive"))
    )
    (net (code "20") (name "/USB0_N") (class "Default")
      (node (ref "R62") (pin "1") (pinfunction "1_1") (pintype "passive"))
      (node (ref "R63") (pin "1") (pinfunction "1_1") (pintype "passive"))
    )
    (net (code "21") (name "/USB0_P") (class "Default")
      (node (ref "R65") (pin "1") (pinfunction "1_1") (pintype "passive"))
      (node (ref "R67") (pin "1") (pinfunction "1_1") (pintype "passive"))
    )
    (net (code "22") (name "/USB1_CON_N") (class "Default")
      (node (ref "D8") (pin "2") (pinfunction "2_2") (pintype "passive"))
      (node (ref "J20") (pin "2") (pinfunction "2_2") (pintype "passive"))
      (node (ref "L3") (pin "3") (pinfunction "3_3") (pintype "passive"))
    )
    (net (code "23") (name "/USB1_CON_P") (class "Default")
      (node (ref "D8") (pin "4") (pinfunction "4_4") (pintype "passive"))
      (node (ref "J20") (pin "3") (pinfunction "3_3") (pintype "passive"))
      (node (ref "L3") (pin "4") (pinfunction "4_4") (pintype "passive"))
    )
    (net (code "24") (name "/USB1_L_N") (class "Default")
      (node (ref "L3") (pin "2") (pinfunction "2_2") (pintype "passive"))
      (node (ref "R64") (pin "2") (pinfunction "2_2") (pintype "passive"))
    )
    (net (code "25") (name "/USB1_L_P") (class "Default")
      (node (ref "L3") (pin "1") (pinfunction "1_1") (pintype "passive"))
      (node (ref "R68") (pin "2") (pinfunction "2_2") (pintype "passive"))
    )
    (net (code "26") (name "/USB1_N") (class "Default")
      (node (ref "R64") (pin "1") (pinfunction "1_1") (pintype "passive"))
      (node (ref "R66") (pin "1") (pinfunction "1_1") (pintype "passive"))
    )
    (net (code "27") (name "/USB1_P") (class "Default")
      (node (ref "R68") (pin "1") (pinfunction "1_1") (pintype "passive"))
      (node (ref "R69") (pin "1") (pinfunction "1_1") (pintype "passive"))
    )
    (net (code "28") (name "/USB1_PWR_EN") (class "Default")
      (node (ref "U12") (pin "4") (pinfunction "ENB_4") (pintype "passive"))
    )
    (net (code "29") (name "/USBDN1_CON_N") (class "Default")
      (node (ref "D10") (pin "2") (pinfunction "2_2") (pintype "passive"))
      (node (ref "J22") (pin "2") (pinfunction "D-_2") (pintype "passive"))
      (node (ref "L6") (pin "3") (pinfunction "3_3") (pintype "passive"))
    )
    (net (code "30") (name "/USBDN1_CON_P") (class "Default")
      (node (ref "D10") (pin "4") (pinfunction "4_4") (pintype "passive"))
      (node (ref "J22") (pin "3") (pinfunction "D+_3") (pintype "passive"))
      (node (ref "L6") (pin "4") (pinfunction "4_4") (pintype "passive"))
    )
    (net (code "31") (name "/USBDN1_N") (class "Default")
      (node (ref "L6") (pin "2") (pinfunction "2_2") (pintype "passive"))
      (node (ref "U13") (pin "1") (pinfunction "USBDM_DN1/PRT_DIS_M1_1") (pintype "bidirectional"))
    )
    (net (code "32") (name "/USBDN1_OC") (class "Default")
      (node (ref "R70") (pin "1") (pinfunction "1_1") (pintype "passive"))
      (node (ref "U11") (pin "2") (pinfunction "FLAGA_2") (pintype "passive"))
      (node (ref "U13") (pin "13") (pinfunction "OCS_N1_13") (pintype "passive"))
    )
    (net (code "33") (name "/USBDN1_P") (class "Default")
      (node (ref "L6") (pin "1") (pinfunction "1_1") (pintype "passive"))
      (node (ref "U13") (pin "2") (pinfunction "USBDP_DN1/PRT_DIS_P1_2") (pintype "bidirectional"))
    )
    (net (code "34") (name "/USBDN1_PWR_EN") (class "Default")
      (node (ref "U11") (pin "1") (pinfunction "ENA_1") (pintype "passive"))
      (node (ref "U13") (pin "12") (pinfunction "PRTPWR1/BC_EN1_12") (pintype "output"))
    )
    (net (code "35") (name "/USBDN2_CON_N") (class "Default")
      (node (ref "D11") (pin "2") (pinfunction "2_2") (pintype "passive"))
      (node (ref "J22") (pin "6") (pinfunction "D2-_6") (pintype "passive"))
      (node (ref "L5") (pin "4") (pinfunction "4_4") (pintype "passive"))
    )
    (net (code "36") (name "/USBDN2_CON_P") (class "Default")
      (node (ref "D11") (pin "4") (pinfunction "4_4") (pintype "passive"))
      (node (ref "J22") (pin "7") (pinfunction "D2+_7") (pintype "passive"))
      (node (ref "L5") (pin "3") (pinfunction "3_3") (pintype "passive"))
    )
    (net (code "37") (name "/USBDN2_N") (class "Default")
      (node (ref "L5") (pin "1") (pinfunction "1_1") (pintype "passive"))
      (node (ref "U13") (pin "3") (pinfunction "USBDM_DN2/PRT_DIS_M2_3") (pintype "bidirectional"))
    )
    (net (code "38") (name "/USBDN2_OC") (class "Default")
      (node (ref "R71") (pin "1") (pinfunction "1_1") (pintype "passive"))
      (node (ref "U11") (pin "3") (pinfunction "FLAGB_3") (pintype "passive"))
      (node (ref "U13") (pin "17") (pinfunction "OCS_N2_17") (pintype "passive"))
    )
    (net (code "39") (name "/USBDN2_P") (class "Default")
      (node (ref "L5") (pin "2") (pinfunction "2_2") (pintype "passive"))
      (node (ref "U13") (pin "4") (pinfunction "USBDP_DN2/PRT_DIS_P2_4") (pintype "bidirectional"))
    )
    (net (code "40") (name "/USBDN2_PWR_EN") (class "Default")
      (node (ref "U11") (pin "4") (pinfunction "ENB_4") (pintype "passive"))
      (node (ref "U13") (pin "16") (pinfunction "PRTPWR2/BC_EN2_16") (pintype "output"))
    )
    (net (code "41") (name "/USBDN3_CON_N") (class "Default")
      (node (ref "D13") (pin "2") (pinfunction "2_2") (pintype "passive"))
      (node (ref "J23") (pin "2") (pinfunction "2_2") (pintype "passive"))
      (node (ref "L7") (pin "4") (pinfunction "4_4") (pintype "passive"))
    )
    (net (code "42") (name "/USBDN3_CON_P") (class "Default")
      (node (ref "D13") (pin "4") (pinfunction "4_4") (pintype "passive"))
      (node (ref "J23") (pin "3") (pinfunction "3_3") (pintype "passive"))
      (node (ref "L7") (pin "3") (pinfunction "3_3") (pintype "passive"))
    )
    (net (code "43") (name "/USBDN3_N") (class "Default")
      (node (ref "L7") (pin "1") (pinfunction "1_1") (pintype "passive"))
      (node (ref "U13") (pin "6") (pinfunction "USBDM_DN3/PRT_DIS_M3_6") (pintype "bidirectional"))
    )
    (net (code "44") (name "/USBDN3_OC") (class "Default")
      (node (ref "R72") (pin "1") (pinfunction "1_1") (pintype "passive"))
      (node (ref "U12") (pin "2") (pinfunction "FLAGA_2") (pintype "passive"))
      (node (ref "U13") (pin "19") (pinfunction "OCS_N3_19") (pintype "passive"))
    )
    (net (code "45") (name "/USBDN3_P") (class "Default")
      (node (ref "L7") (pin "2") (pinfunction "2_2") (pintype "passive"))
      (node (ref "U13") (pin "7") (pinfunction "USBDP_DN3/PRT_DIS_P3_7") (pintype "bidirectional"))
    )
    (net (code "46") (name "/USBDN3_PWR_EN") (class "Default")
      (node (ref "U12") (pin "1") (pinfunction "ENA_1") (pintype "passive"))
      (node (ref "U13") (pin "18") (pinfunction "PRTPWR3/BC_EN3_18") (pintype "output"))
    )
    (net (code "47") (name "/USB_MPCIE1_N") (class "Default")
      (node (ref "R66") (pin "2") (pinfunction "2_2") (pintype "passive"))
    )
    (net (code "48") (name "/USB_MPCIE1_P") (class "Default")
      (node (ref "R69") (pin "2") (pinfunction "2_2") (pintype "passive"))
    )
    (net (code "49") (name "/USB_MPCIE2_N") (class "Default")
      (node (ref "U13") (pin "8") (pinfunction "USBDM_DN4/PRT_DIS_M4_8") (pintype "bidirectional"))
    )
    (net (code "50") (name "/USB_MPCIE2_P") (class "Default")
      (node (ref "U13") (pin "9") (pinfunction "USBDP_DN4/PRT_DIS_P4_9") (pintype "bidirectional"))
    )
    (net (code "51") (name "/USB_OC") (class "Default")
      (node (ref "U12") (pin "3") (pinfunction "FLAGB_3") (pintype "passive"))
    )
    (net (code "52") (name "/USB_OTG_CON_N") (class "Default")
      (node (ref "D9") (pin "2") (pinfunction "2_2") (pintype "passive"))
      (node (ref "J21") (pin "2") (pinfunction "P2_2") (pintype "passive"))
      (node (ref "L4") (pin "3") (pinfunction "3_3") (pintype "passive"))
    )
    (net (code "53") (name "/USB_OTG_CON_P") (class "Default")
      (node (ref "D9") (pin "4") (pinfunction "4_4") (pintype "passive"))
      (node (ref "J21") (pin "3") (pinfunction "P3_3") (pintype "passive"))
      (node (ref "L4") (pin "4") (pinfunction "4_4") (pintype "passive"))
    )
    (net (code "54") (name "/USB_OTG_N") (class "Default")
      (node (ref "L4") (pin "2") (pinfunction "2_2") (pintype "passive"))
      (node (ref "R62") (pin "2") (pinfunction "2_2") (pintype "passive"))
    )
    (net (code "55") (name "/USB_OTG_P") (class "Default")
      (node (ref "L4") (pin "1") (pinfunction "1_1") (pintype "passive"))
      (node (ref "R65") (pin "2") (pinfunction "2_2") (pintype "passive"))
    )
    (net (code "56") (name "/USB_UP_N") (class "Default")
      (node (ref "R63") (pin "2") (pinfunction "2_2") (pintype "passive"))
      (node (ref "U13") (pin "30") (pinfunction "USBDM_UP_30") (pintype "bidirectional"))
    )
    (net (code "57") (name "/USB_UP_P") (class "Default")
      (node (ref "R67") (pin "2") (pinfunction "2_2") (pintype "passive"))
      (node (ref "U13") (pin "31") (pinfunction "USBDP_UP_31") (pintype "bidirectional"))
    )
    (net (code "58") (name "/USB_XTALIN") (class "Default")
      (node (ref "C99") (pin "2") (pinfunction "2_2") (pintype "passive"))
      (node (ref "R23") (pin "2") (pinfunction "2_2") (pintype "passive"))
      (node (ref "U13") (pin "33") (pinfunction "XTALIN/CLKIN_33") (pintype "passive"))
      (node (ref "Y2") (pin "2") (pinfunction "2_2") (pintype "passive"))
    )
    (net (code "59") (name "/USB_XTALOUT") (class "Default")
      (node (ref "C100") (pin "2") (pinfunction "2_2") (pintype "passive"))
      (node (ref "R23") (pin "1") (pinfunction "1_1") (pintype "passive"))
      (node (ref "U13") (pin "32") (pinfunction "XTALOUT_32") (pintype "passive"))
      (node (ref "Y2") (pin "1") (pinfunction "1_1") (pintype "passive"))
    )
    (net (code "60") (name "/VBUS_DET") (class "Default")
      (node (ref "R169") (pin "1") (pinfunction "1_1") (pintype "passive"))
      (node (ref "R75") (pin "2") (pinfunction "2_2") (pintype "passive"))
      (node (ref "R76") (pin "1") (pinfunction "1_1") (pintype "passive"))
      (node (ref "U13") (pin "27") (pinfunction "VBUS_DET_27") (pintype "passive"))
    )
    (net (code "61") (name "GND") (class "Default")
      (node (ref "C100") (pin "1") (pinfunction "1_1") (pintype "passive"))
      (node (ref "C101") (pin "2") (pinfunction "2_2") (pintype "passive"))
      (node (ref "C102") (pin "1") (pinfunction "1_1") (pintype "passive"))
      (node (ref "C103") (pin "2") (pinfunction "2_2") (pintype "passive"))
      (node (ref "C104") (pin "1") (pinfunction "1_1") (pintype "passive"))
      (node (ref "C105") (pin "2") (pinfunction "2_2") (pintype "passive"))
      (node (ref "C107") (pin "2") (pinfunction "2_2") (pintype "passive"))
      (node (ref "C109") (pin "2") (pinfunction "2_2") (pintype "passive"))
      (node (ref "C110") (pin "2") (pinfunction "2_2") (pintype "passive"))
      (node (ref "C111") (pin "2") (pinfunction "2_2") (pintype "passive"))
      (node (ref "C112") (pin "2") (pinfunction "2_2") (pintype "passive"))
      (node (ref "C113") (pin "1") (pinfunction "1_1") (pintype "passive"))
      (node (ref "C85") (pin "2") (pinfunction "2_2") (pintype "passive"))
      (node (ref "C86") (pin "2") (pinfunction "2_2") (pintype "passive"))
      (node (ref "C87") (pin "2") (pinfunction "2_2") (pintype "passive"))
      (node (ref "C88") (pin "2") (pinfunction "2_2") (pintype "passive"))
      (node (ref "C89") (pin "2") (pinfunction "2_2") (pintype "passive"))
      (node (ref "C90") (pin "2") (pinfunction "2_2") (pintype "passive"))
      (node (ref "C91") (pin "2") (pinfunction "2_2") (pintype "passive"))
      (node (ref "C92") (pin "2") (pinfunction "2_2") (pintype "passive"))
      (node (ref "C93") (pin "2") (pinfunction "2_2") (pintype "passive"))
      (node (ref "C94") (pin "2") (pinfunction "2_2") (pintype "passive"))
      (node (ref "C95") (pin "2") (pinfunction "2_2") (pintype "passive"))
      (node (ref "C96") (pin "2") (pinfunction "2_2") (pintype "passive"))
      (node (ref "C97") (pin "2") (pinfunction "2_2") (pintype "passive"))
      (node (ref "C98") (pin "2") (pinfunction "2_2") (pintype "passive"))
      (node (ref "C99") (pin "1") (pinfunction "1_1") (pintype "passive"))
      (node (ref "D10") (pin "3") (pinfunction "3_3") (pintype "passive"))
      (node (ref "D11") (pin "3") (pinfunction "3_3") (pintype "passive"))
      (node (ref "D12") (pin "1") (pinfunction "cathode_1") (pintype "passive"))
      (node (ref "D13") (pin "3") (pinfunction "3_3") (pintype "passive"))
      (node (ref "D19") (pin "2") (pinfunction "2_2") (pintype "passive"))
      (node (ref "D8") (pin "3") (pinfunction "3_3") (pintype "passive"))
      (node (ref "D9") (pin "3") (pinfunction "3_3") (pintype "passive"))
      (node (ref "J20") (pin "4") (pinfunction "4_4") (pintype "passive"))
      (node (ref "J21") (pin "10") (pinfunction "10_10") (pintype "passive"))
      (node (ref "J21") (pin "11") (pinfunction "11_11") (pintype "passive"))
      (node (ref "J21") (pin "5") (pinfunction "P5_5") (pintype "passive"))
      (node (ref "J21") (pin "6") (pinfunction "6_6") (pintype "passive"))
      (node (ref "J21") (pin "7") (pinfunction "7_7") (pintype "passive"))
      (node (ref "J21") (pin "8") (pinfunction "8_8") (pintype "passive"))
      (node (ref "J21") (pin "9") (pinfunction "9_9") (pintype "passive"))
      (node (ref "J22") (pin "10") (pinfunction "SHIELD_10") (pintype "passive"))
      (node (ref "J22") (pin "11") (pinfunction "SHIELD_11") (pintype "passive"))
      (node (ref "J22") (pin "12") (pinfunction "SHIELD_12") (pintype "passive"))
      (node (ref "J22") (pin "4") (pinfunction "GND_4") (pintype "passive"))
      (node (ref "J22") (pin "8") (pinfunction "GND_8") (pintype "passive"))
      (node (ref "J22") (pin "9") (pinfunction "SHIELD_9") (pintype "passive"))
      (node (ref "J23") (pin "4") (pinfunction "4_4") (pintype "passive"))
      (node (ref "JP1") (pin "2") (pinfunction "2_2") (pintype "passive"))
      (node (ref "R74") (pin "2") (pinfunction "2_2") (pintype "passive"))
      (node (ref "R76") (pin "2") (pinfunction "2_2") (pintype "passive"))
      (node (ref "R79") (pin "1") (pinfunction "1_1") (pintype "passive"))
      (node (ref "R80") (pin "1") (pinfunction "1_1") (pintype "passive"))
      (node (ref "R81") (pin "2") (pinfunction "2_2") (pintype "passive"))
      (node (ref "R82") (pin "1") (pinfunction "1_1") (pintype "passive"))
      (node (ref "R83") (pin "1") (pinfunction "1_1") (pintype "passive"))
      (node (ref "U11") (pin "6") (pinfunction "GND_6") (pintype "power_in"))
      (node (ref "U12") (pin "6") (pinfunction "GND_6") (pintype "power_in"))
      (node (ref "U13") (pin "11") (pinfunction "TEST_11") (pintype "passive"))
      (node (ref "U13") (pin "37") (pinfunction "EPAD_37") (pintype "passive"))
    )
    (net (code "62") (name "unconnected-(U13-OCS_N4-Pad21)") (class "Default")
      (node (ref "U13") (pin "21") (pinfunction "OCS_N4_21") (pintype "passive+no_connect"))
    )
    (net (code "63") (name "unconnected-(U13-PRTPWR4{slash}BC_EN4-Pad20)") (class "Default")
      (node (ref "U13") (pin "20") (pinfunction "PRTPWR4/BC_EN4_20") (pintype "output+no_connect"))
    )
  )
)
